# SeedUP_Nano_Controller_2020-11-19_18-19-.net
KiCad netlist of a schematic drawn in EasyEDA
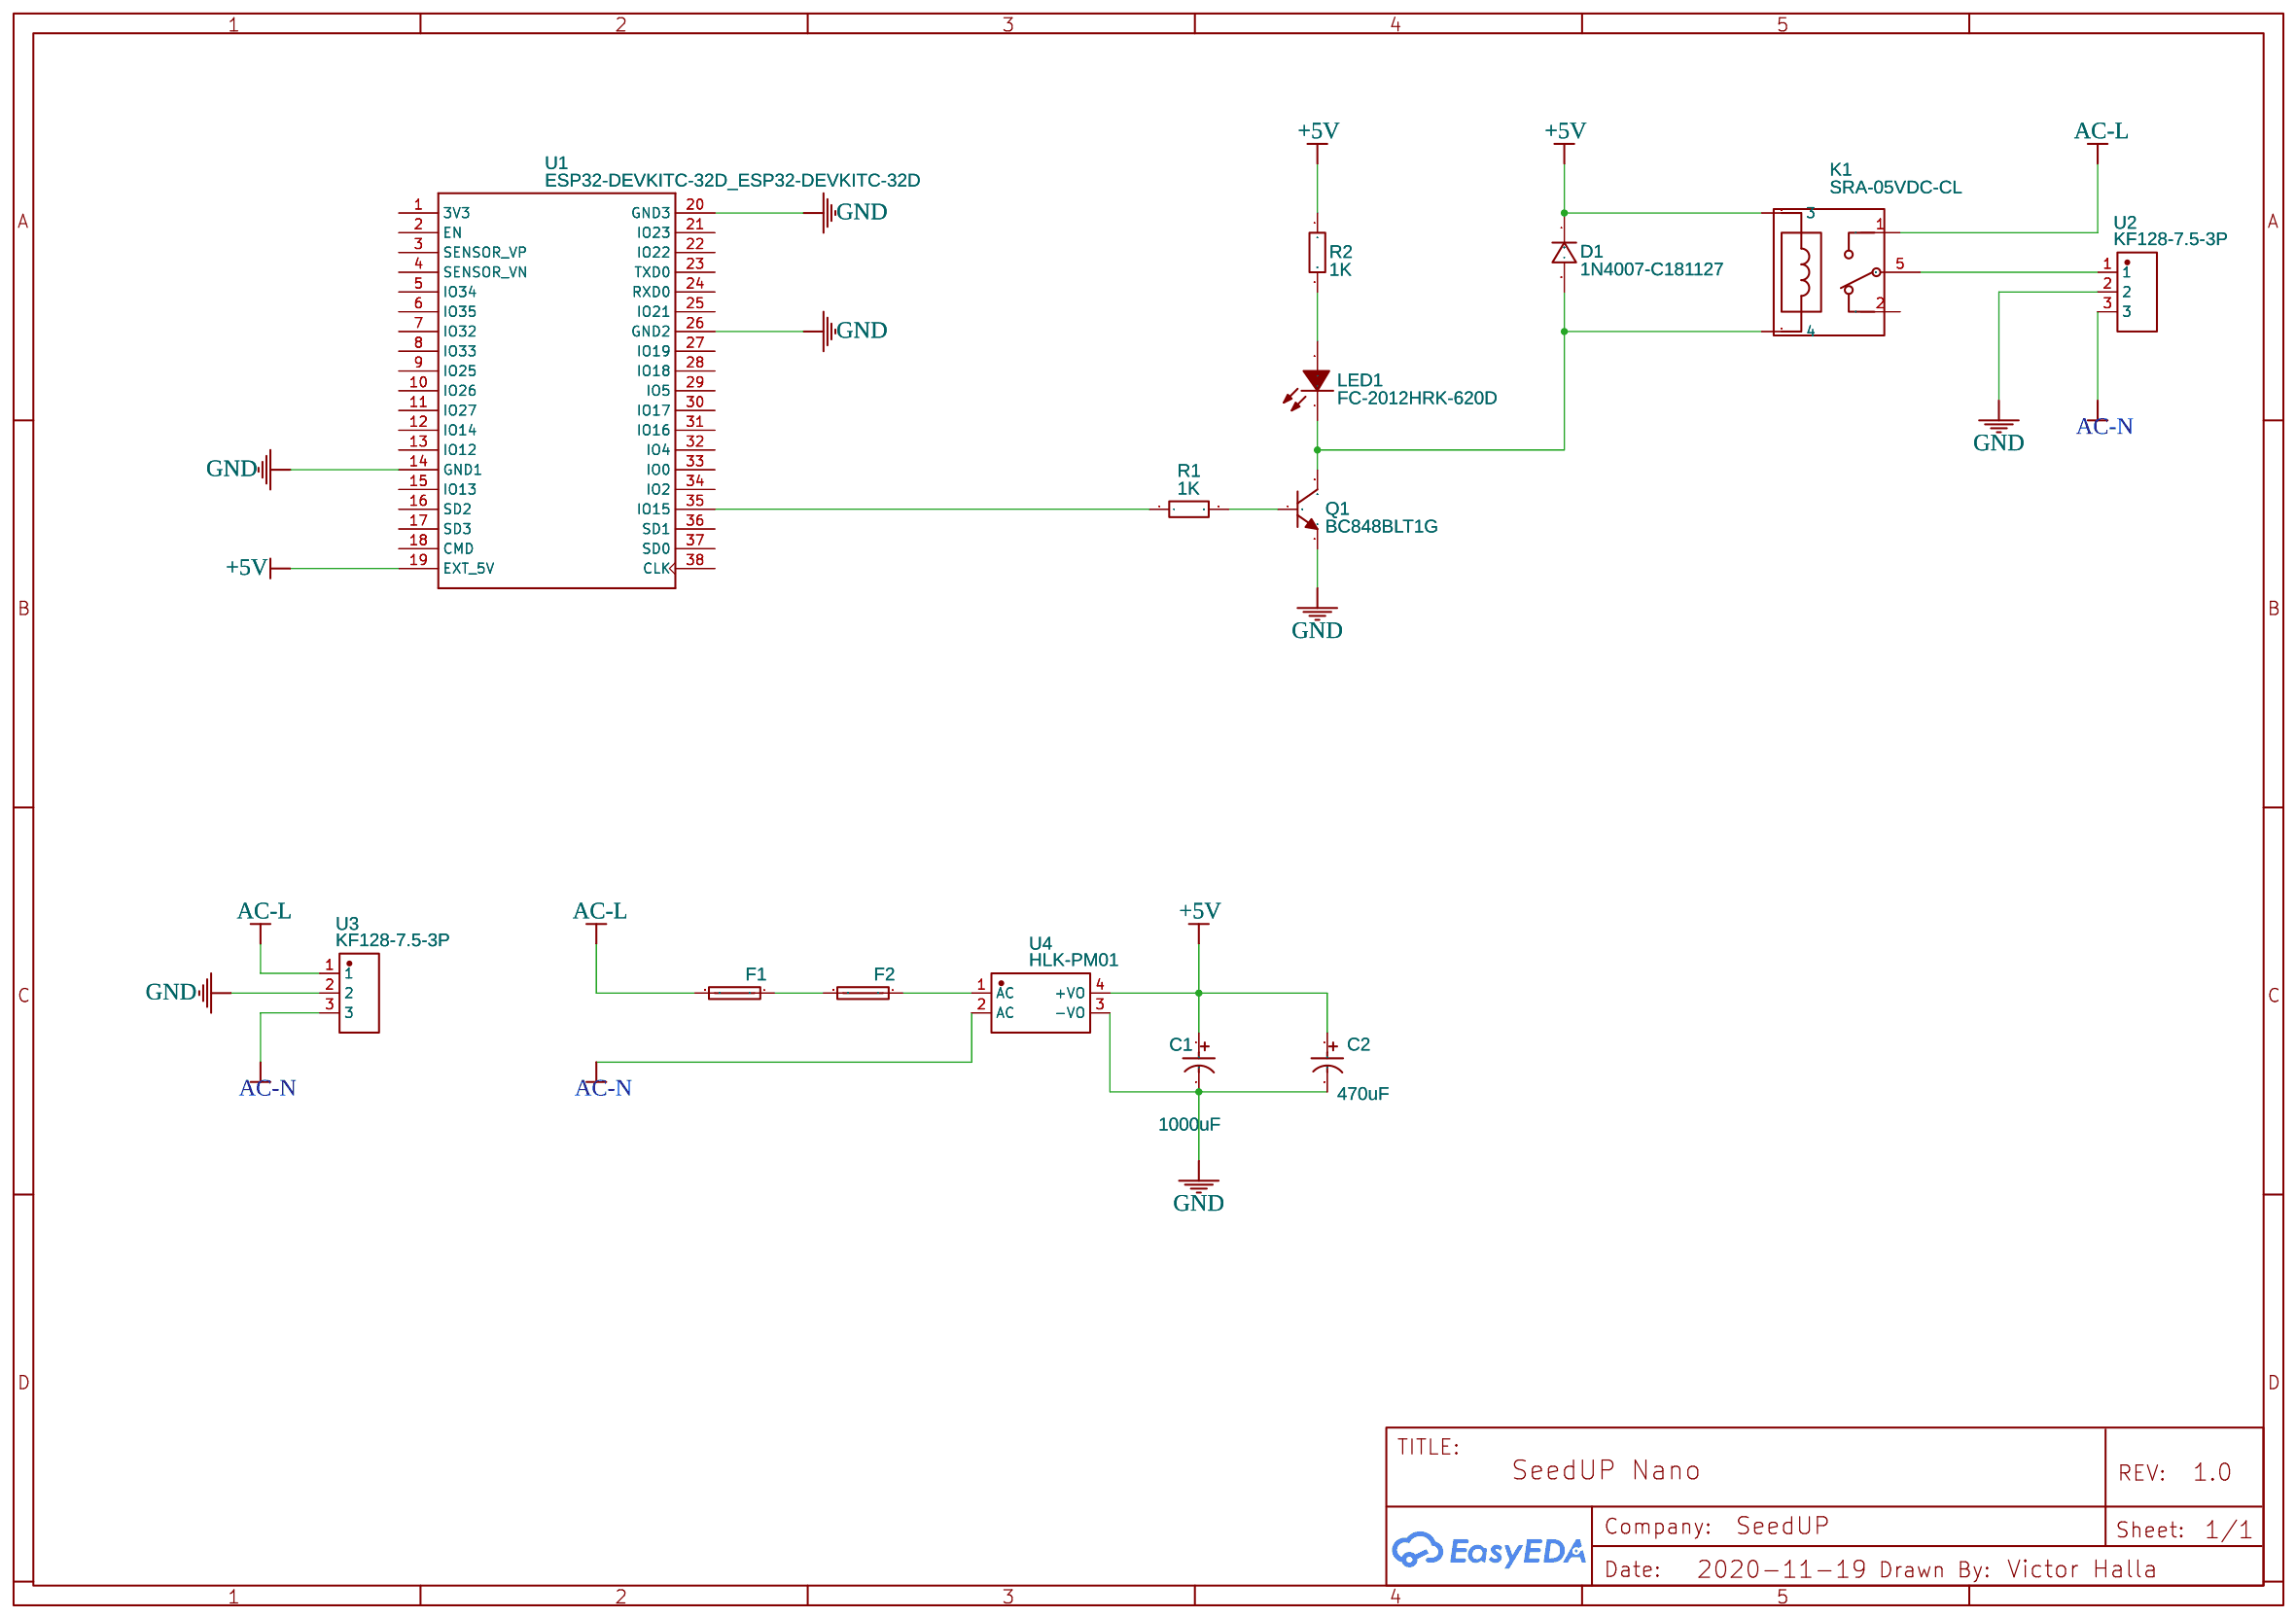
[diagram p0: schematic sheet]

(export (version "E")
  (design (tool "Eeschema 10.0.6"))
  (components
    (comp (ref "C1")
      (value "1000uF")
      (fields
        (field (name "BOM_Manufacturer Part") "RVT0J102M0810")
        (field (name "BOM_Supplier Part") "C42851")
      )
      (libsource (lib "") (part "Unknown_600_-275"))
    )
    (comp (ref "C2")
      (value "470uF")
      (fields
        (field (name "BOM_Manufacturer Part") "MV471M6R3F105R")
        (field (name "BOM_Supplier Part") "C65208")
      )
      (libsource (lib "") (part "Unknown_665_-275"))
    )
    (comp (ref "D1")
      (value "1N4007-C181127")
      (fields (field (name "BOM_Manufacturer Part") "1N4007") (field (name "BOM_Supplier Part") "C181127"))
      (libsource (lib "") (part "1N4007-C181127"))
    )
    (comp (ref "F1")
      (value "F1")
      (fields
        (field (name "BOM_Manufacturer Part") "300mA 250VAC")
        (field (name "BOM_Supplier Part") "C12107")
      )
      (libsource (lib "") (part "Unknown_365_-310"))
    )
    (comp (ref "F2")
      (value "F2")
      (fields
        (field (name "BOM_Manufacturer Part") "72*C Thermal Fuse")
        (field (name "BOM_Supplier Part") "C12107")
      )
      (libsource (lib "") (part "Unknown_430_-310"))
    )
    (comp (ref "K1")
      (value "SRA-05VDC-CL")
      (fields (field (name "BOM_Supplier Part") "C99666"))
      (libsource (lib "") (part "SRA-05VDC-CL"))
    )
    (comp (ref "LED1")
      (value "FC-2012HRK-620D")
      (fields (field (name "BOM_Supplier Part") "C84256"))
      (libsource (lib "") (part "FC-2012HRK-620D"))
    )
    (comp (ref "Q1")
      (value "BC848BLT1G")
      (fields (field (name "BOM_Supplier Part") "C163725"))
      (libsource (lib "") (part "BC848BLT1G"))
    )
    (comp (ref "R1")
      (value "1K")
      (fields
        (field (name "BOM_Manufacturer Part") "0603WAD1001T5E")
        (field (name "BOM_Supplier Part") "C51218")
      )
      (libsource (lib "") (part "0603WAD1001T5E"))
    )
    (comp (ref "R2")
      (value "1K")
      (fields
        (field (name "BOM_Manufacturer Part") "0603WAD1001T5E")
        (field (name "BOM_Supplier Part") "C51218")
      )
      (libsource (lib "") (part "0603WAD1001T5E_1"))
    )
    (comp (ref "U1")
      (value "ESP32-DEVKITC-32D_ESP32-DEVKITC-32D")
      (libsource (lib "") (part "ESP32-DEVKITC-32D_ESP32-DEVKITC-32D"))
    )
    (comp (ref "U2")
      (value "KF128-7.5-3P")
      (fields (field (name "BOM_Supplier Part") "C474955"))
      (libsource (lib "") (part "KF128-7.5-3P"))
    )
    (comp (ref "U3")
      (value "KF128-7.5-3P")
      (fields (field (name "BOM_Supplier Part") "C474955"))
      (libsource (lib "") (part "KF128-7.5-3P"))
    )
    (comp (ref "U4")
      (value "HLK-PM01")
      (fields (field (name "BOM_Supplier Part") "C209903"))
      (libsource (lib "") (part "HLK-PM01"))
    )
  )
  (nets
    (net (code "1") (name "+5V") (class "Default")
      (node (ref "C1") (pin "1") (pinfunction "1_1") (pintype "input"))
      (node (ref "C2") (pin "1") (pinfunction "1_1") (pintype "input"))
      (node (ref "D1") (pin "1") (pinfunction "C_1") (pintype "unspecified"))
      (node (ref "K1") (pin "3") (pinfunction "3_3") (pintype "unspecified"))
      (node (ref "R2") (pin "1") (pinfunction "1_1") (pintype "input"))
      (node (ref "U1") (pin "19") (pinfunction "EXT_5V_19") (pintype "bidirectional"))
      (node (ref "U4") (pin "4") (pinfunction "+VO_4") (pintype "unspecified"))
    )
    (net (code "2") (name "AC-L") (class "Default")
      (node (ref "F1") (pin "2") (pinfunction "2_2") (pintype "unspecified"))
      (node (ref "K1") (pin "1") (pinfunction "1_1") (pintype "unspecified"))
      (node (ref "U3") (pin "1") (pinfunction "1_1") (pintype "unspecified"))
    )
    (net (code "3") (name "AC-N") (class "Default")
      (node (ref "U2") (pin "3") (pinfunction "3_3") (pintype "unspecified"))
      (node (ref "U3") (pin "3") (pinfunction "3_3") (pintype "unspecified"))
      (node (ref "U4") (pin "2") (pinfunction "AC_2") (pintype "unspecified"))
    )
    (net (code "4") (name "GND") (class "Default")
      (node (ref "C1") (pin "2") (pinfunction "2_2") (pintype "input"))
      (node (ref "C2") (pin "2") (pinfunction "2_2") (pintype "input"))
      (node (ref "Q1") (pin "2") (pinfunction "E_2") (pintype "input"))
      (node (ref "U1") (pin "14") (pinfunction "GND1_14") (pintype "bidirectional"))
      (node (ref "U1") (pin "20") (pinfunction "GND3_20") (pintype "bidirectional"))
      (node (ref "U1") (pin "26") (pinfunction "GND2_26") (pintype "bidirectional"))
      (node (ref "U2") (pin "2") (pinfunction "2_2") (pintype "unspecified"))
      (node (ref "U3") (pin "2") (pinfunction "2_2") (pintype "unspecified"))
      (node (ref "U4") (pin "3") (pinfunction "-VO_3") (pintype "unspecified"))
    )
    (net (code "5") (name "Net-(D1-A)") (class "Default")
      (node (ref "D1") (pin "2") (pinfunction "A_2") (pintype "unspecified"))
      (node (ref "K1") (pin "4") (pinfunction "4_4") (pintype "unspecified"))
      (node (ref "LED1") (pin "1") (pinfunction "-_1") (pintype "unspecified"))
      (node (ref "Q1") (pin "3") (pinfunction "C_3") (pintype "input"))
    )
    (net (code "6") (name "Net-(F1-Pad1)") (class "Default")
      (node (ref "F1") (pin "1") (pinfunction "1_1") (pintype "unspecified"))
      (node (ref "F2") (pin "2") (pinfunction "2_2") (pintype "unspecified"))
    )
    (net (code "7") (name "Net-(F2-Pad1)") (class "Default")
      (node (ref "F2") (pin "1") (pinfunction "1_1") (pintype "unspecified"))
      (node (ref "U4") (pin "1") (pinfunction "AC_1") (pintype "unspecified"))
    )
    (net (code "8") (name "Net-(K1-Pad5)") (class "Default")
      (node (ref "K1") (pin "5") (pinfunction "5_5") (pintype "unspecified"))
      (node (ref "U2") (pin "1") (pinfunction "1_1") (pintype "unspecified"))
    )
    (net (code "9") (name "Net-(LED1-+)") (class "Default")
      (node (ref "LED1") (pin "2") (pinfunction "+_2") (pintype "unspecified"))
      (node (ref "R2") (pin "2") (pinfunction "2_2") (pintype "input"))
    )
    (net (code "10") (name "Net-(Q1-B)") (class "Default")
      (node (ref "Q1") (pin "1") (pinfunction "B_1") (pintype "input"))
      (node (ref "R1") (pin "2") (pinfunction "2_2") (pintype "input"))
    )
    (net (code "11") (name "Net-(U1-IO15)") (class "Default")
      (node (ref "R1") (pin "1") (pinfunction "1_1") (pintype "input"))
      (node (ref "U1") (pin "35") (pinfunction "IO15_35") (pintype "bidirectional"))
    )
    (net (code "12") (name "unconnected-(K1-Pad2)") (class "Default")
      (node (ref "K1") (pin "2") (pinfunction "2_2") (pintype "unspecified"))
    )
    (net (code "13") (name "unconnected-(U1-3V3-Pad1)") (class "Default")
      (node (ref "U1") (pin "1") (pinfunction "3V3_1") (pintype "bidirectional"))
    )
    (net (code "14") (name "unconnected-(U1-CLK-Pad38)") (class "Default")
      (node (ref "U1") (pin "38") (pinfunction "CLK_38") (pintype "input"))
    )
    (net (code "15") (name "unconnected-(U1-CMD-Pad18)") (class "Default")
      (node (ref "U1") (pin "18") (pinfunction "CMD_18") (pintype "bidirectional"))
    )
    (net (code "16") (name "unconnected-(U1-EN-Pad2)") (class "Default")
      (node (ref "U1") (pin "2") (pinfunction "EN_2") (pintype "input"))
    )
    (net (code "17") (name "unconnected-(U1-IO0-Pad33)") (class "Default")
      (node (ref "U1") (pin "33") (pinfunction "IO0_33") (pintype "bidirectional"))
    )
    (net (code "18") (name "unconnected-(U1-IO2-Pad34)") (class "Default")
      (node (ref "U1") (pin "34") (pinfunction "IO2_34") (pintype "bidirectional"))
    )
    (net (code "19") (name "unconnected-(U1-IO4-Pad32)") (class "Default")
      (node (ref "U1") (pin "32") (pinfunction "IO4_32") (pintype "bidirectional"))
    )
    (net (code "20") (name "unconnected-(U1-IO5-Pad29)") (class "Default")
      (node (ref "U1") (pin "29") (pinfunction "IO5_29") (pintype "bidirectional"))
    )
    (net (code "21") (name "unconnected-(U1-IO12-Pad13)") (class "Default")
      (node (ref "U1") (pin "13") (pinfunction "IO12_13") (pintype "bidirectional"))
    )
    (net (code "22") (name "unconnected-(U1-IO13-Pad15)") (class "Default")
      (node (ref "U1") (pin "15") (pinfunction "IO13_15") (pintype "bidirectional"))
    )
    (net (code "23") (name "unconnected-(U1-IO14-Pad12)") (class "Default")
      (node (ref "U1") (pin "12") (pinfunction "IO14_12") (pintype "bidirectional"))
    )
    (net (code "24") (name "unconnected-(U1-IO16-Pad31)") (class "Default")
      (node (ref "U1") (pin "31") (pinfunction "IO16_31") (pintype "bidirectional"))
    )
    (net (code "25") (name "unconnected-(U1-IO17-Pad30)") (class "Default")
      (node (ref "U1") (pin "30") (pinfunction "IO17_30") (pintype "bidirectional"))
    )
    (net (code "26") (name "unconnected-(U1-IO18-Pad28)") (class "Default")
      (node (ref "U1") (pin "28") (pinfunction "IO18_28") (pintype "bidirectional"))
    )
    (net (code "27") (name "unconnected-(U1-IO19-Pad27)") (class "Default")
      (node (ref "U1") (pin "27") (pinfunction "IO19_27") (pintype "bidirectional"))
    )
    (net (code "28") (name "unconnected-(U1-IO21-Pad25)") (class "Default")
      (node (ref "U1") (pin "25") (pinfunction "IO21_25") (pintype "bidirectional"))
    )
    (net (code "29") (name "unconnected-(U1-IO22-Pad22)") (class "Default")
      (node (ref "U1") (pin "22") (pinfunction "IO22_22") (pintype "bidirectional"))
    )
    (net (code "30") (name "unconnected-(U1-IO23-Pad21)") (class "Default")
      (node (ref "U1") (pin "21") (pinfunction "IO23_21") (pintype "bidirectional"))
    )
    (net (code "31") (name "unconnected-(U1-IO25-Pad9)") (class "Default")
      (node (ref "U1") (pin "9") (pinfunction "IO25_9") (pintype "bidirectional"))
    )
    (net (code "32") (name "unconnected-(U1-IO26-Pad10)") (class "Default")
      (node (ref "U1") (pin "10") (pinfunction "IO26_10") (pintype "bidirectional"))
    )
    (net (code "33") (name "unconnected-(U1-IO27-Pad11)") (class "Default")
      (node (ref "U1") (pin "11") (pinfunction "IO27_11") (pintype "bidirectional"))
    )
    (net (code "34") (name "unconnected-(U1-IO32-Pad7)") (class "Default")
      (node (ref "U1") (pin "7") (pinfunction "IO32_7") (pintype "bidirectional"))
    )
    (net (code "35") (name "unconnected-(U1-IO33-Pad8)") (class "Default")
      (node (ref "U1") (pin "8") (pinfunction "IO33_8") (pintype "bidirectional"))
    )
    (net (code "36") (name "unconnected-(U1-IO34-Pad5)") (class "Default")
      (node (ref "U1") (pin "5") (pinfunction "IO34_5") (pintype "bidirectional"))
    )
    (net (code "37") (name "unconnected-(U1-IO35-Pad6)") (class "Default")
      (node (ref "U1") (pin "6") (pinfunction "IO35_6") (pintype "bidirectional"))
    )
    (net (code "38") (name "unconnected-(U1-RXD0-Pad24)") (class "Default")
      (node (ref "U1") (pin "24") (pinfunction "RXD0_24") (pintype "input"))
    )
    (net (code "39") (name "unconnected-(U1-SD0-Pad37)") (class "Default")
      (node (ref "U1") (pin "37") (pinfunction "SD0_37") (pintype "bidirectional"))
    )
    (net (code "40") (name "unconnected-(U1-SD1-Pad36)") (class "Default")
      (node (ref "U1") (pin "36") (pinfunction "SD1_36") (pintype "bidirectional"))
    )
    (net (code "41") (name "unconnected-(U1-SD2-Pad16)") (class "Default")
      (node (ref "U1") (pin "16") (pinfunction "SD2_16") (pintype "bidirectional"))
    )
    (net (code "42") (name "unconnected-(U1-SD3-Pad17)") (class "Default")
      (node (ref "U1") (pin "17") (pinfunction "SD3_17") (pintype "bidirectional"))
    )
    (net (code "43") (name "unconnected-(U1-SENSOR_VN-Pad4)") (class "Default")
      (node (ref "U1") (pin "4") (pinfunction "SENSOR_VN_4") (pintype "input"))
    )
    (net (code "44") (name "unconnected-(U1-SENSOR_VP-Pad3)") (class "Default")
      (node (ref "U1") (pin "3") (pinfunction "SENSOR_VP_3") (pintype "input"))
    )
    (net (code "45") (name "unconnected-(U1-TXD0-Pad23)") (class "Default")
      (node (ref "U1") (pin "23") (pinfunction "TXD0_23") (pintype "output"))
    )
  )
)
